# STM32H730_PINOUT.net
KiCad netlist of a schematic drawn in Altium Designer
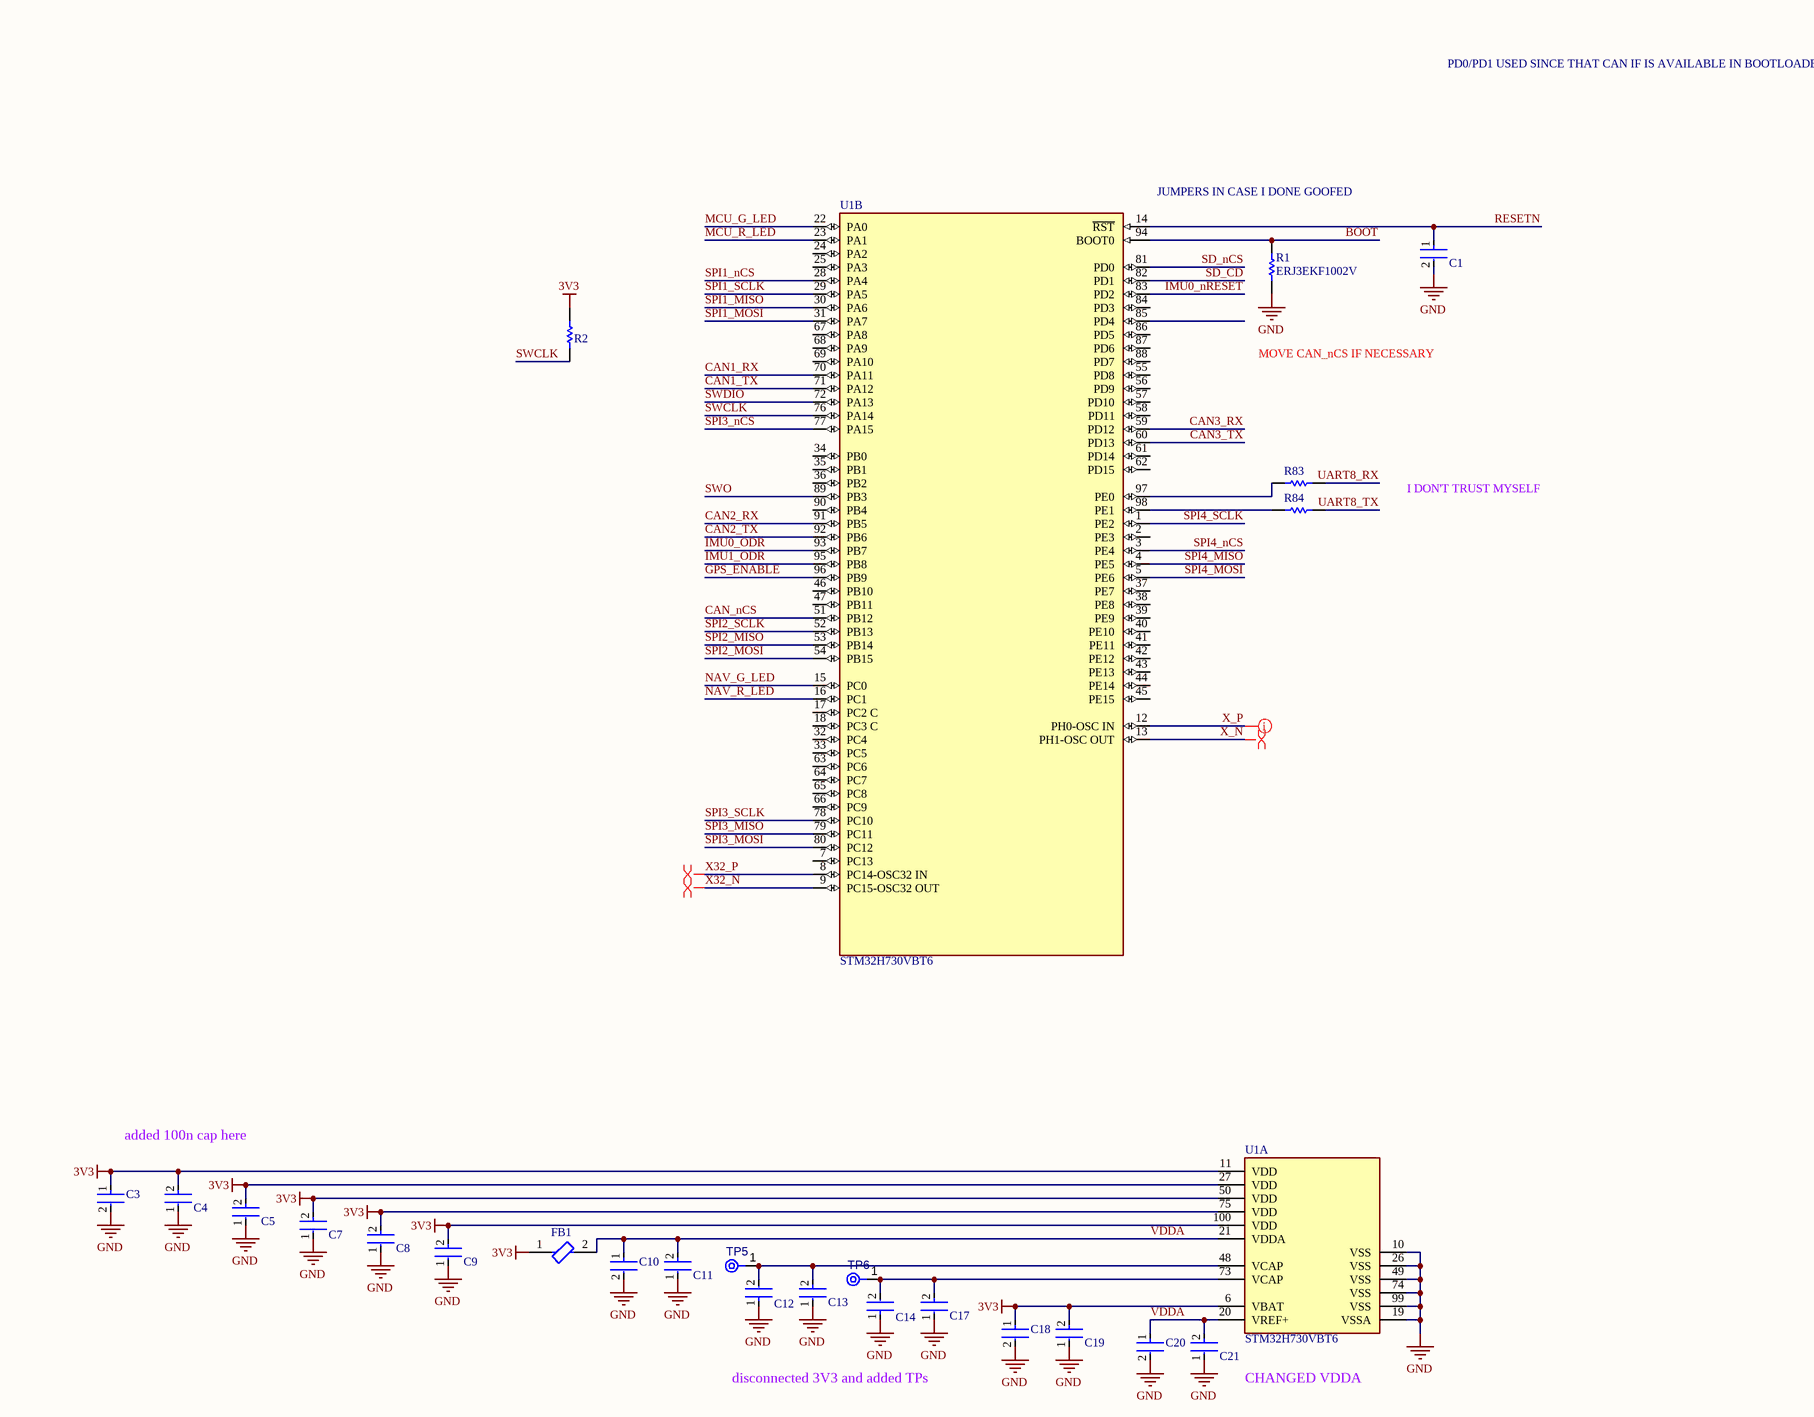
[diagram p0: STM32H730_PINOUT.SchDoc, top left]
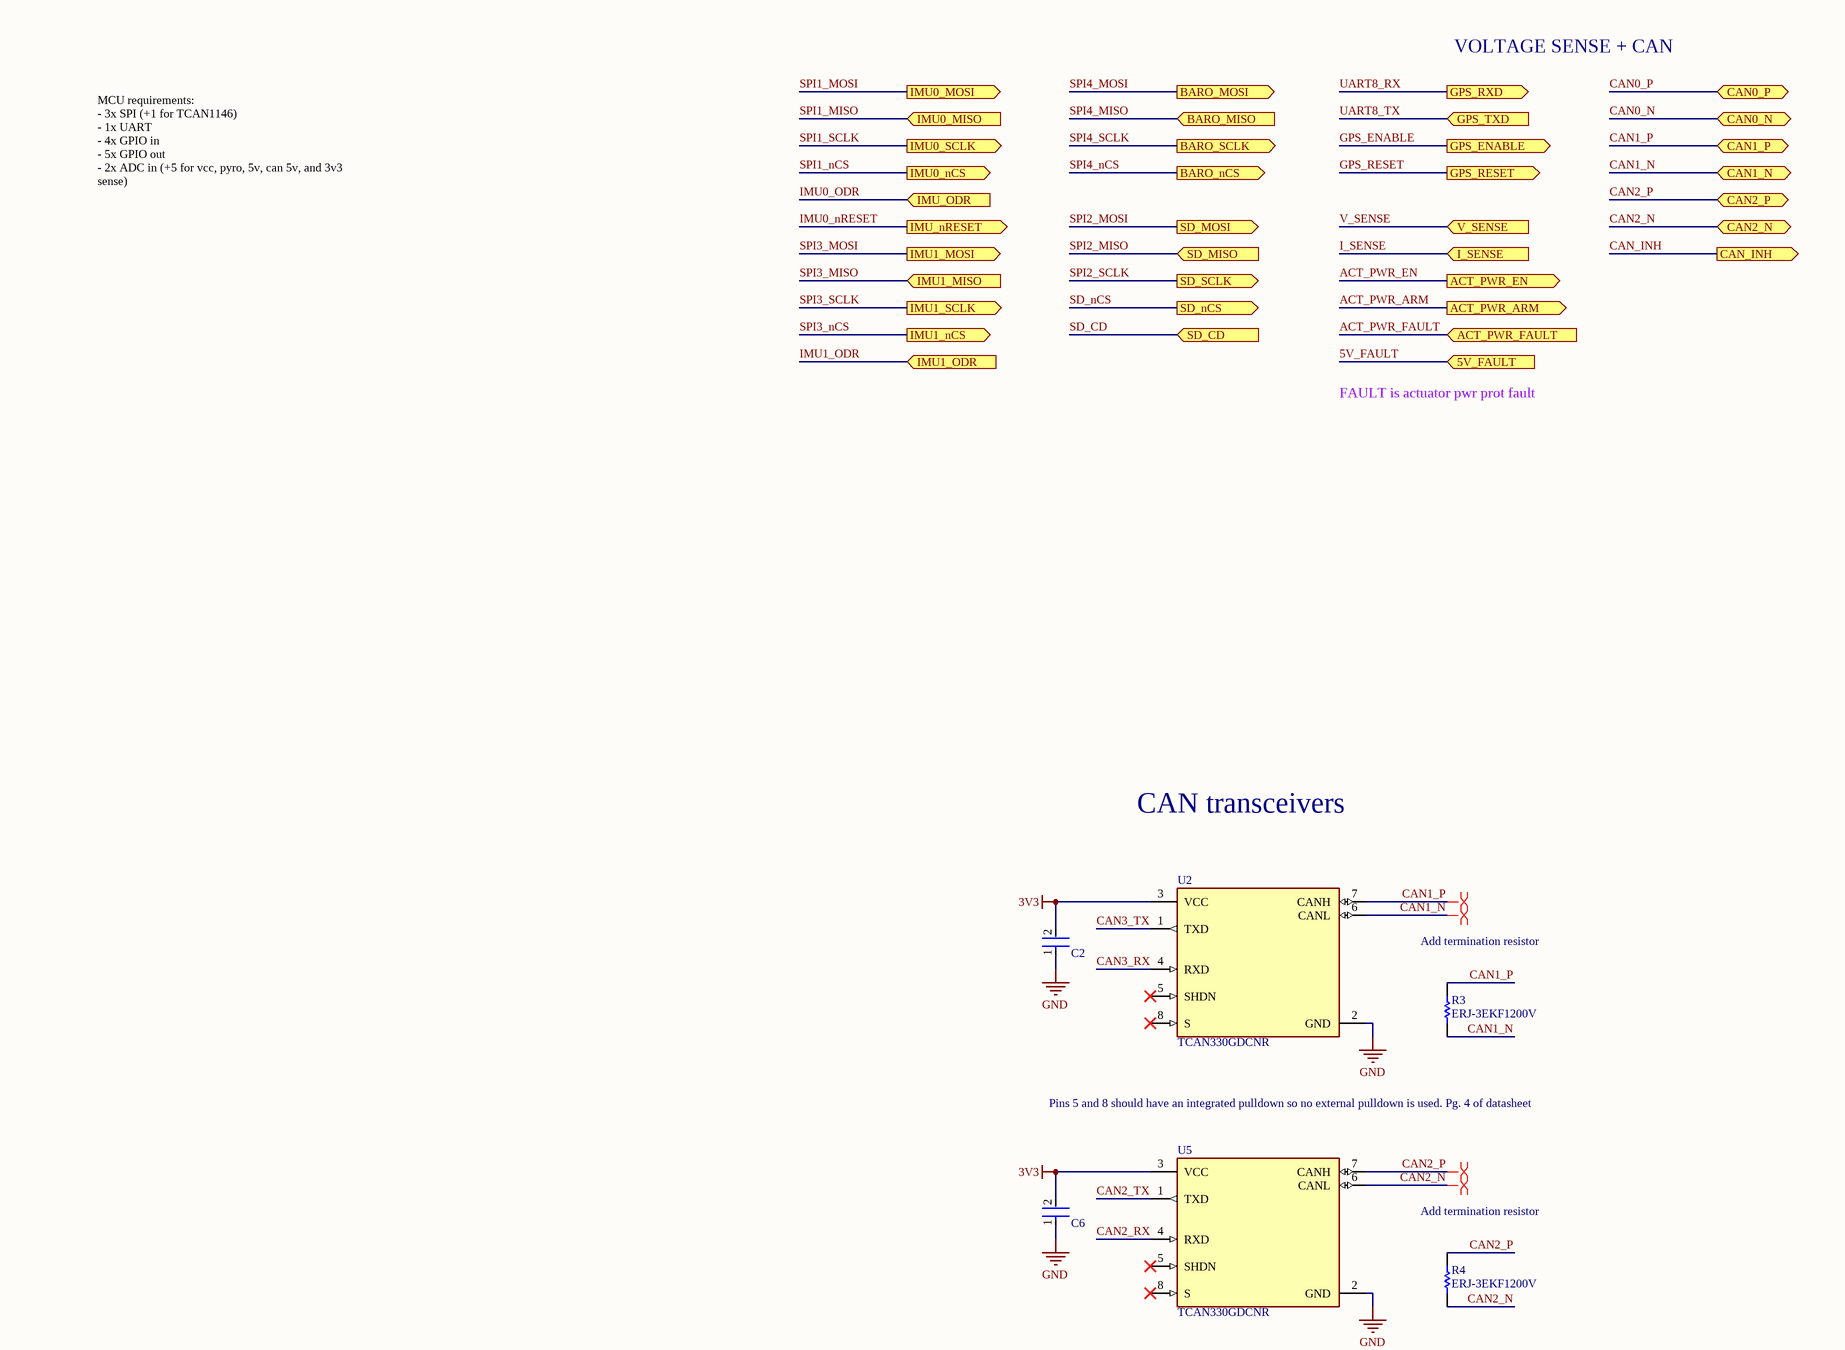
[diagram p1: STM32H730_PINOUT.SchDoc, top right]
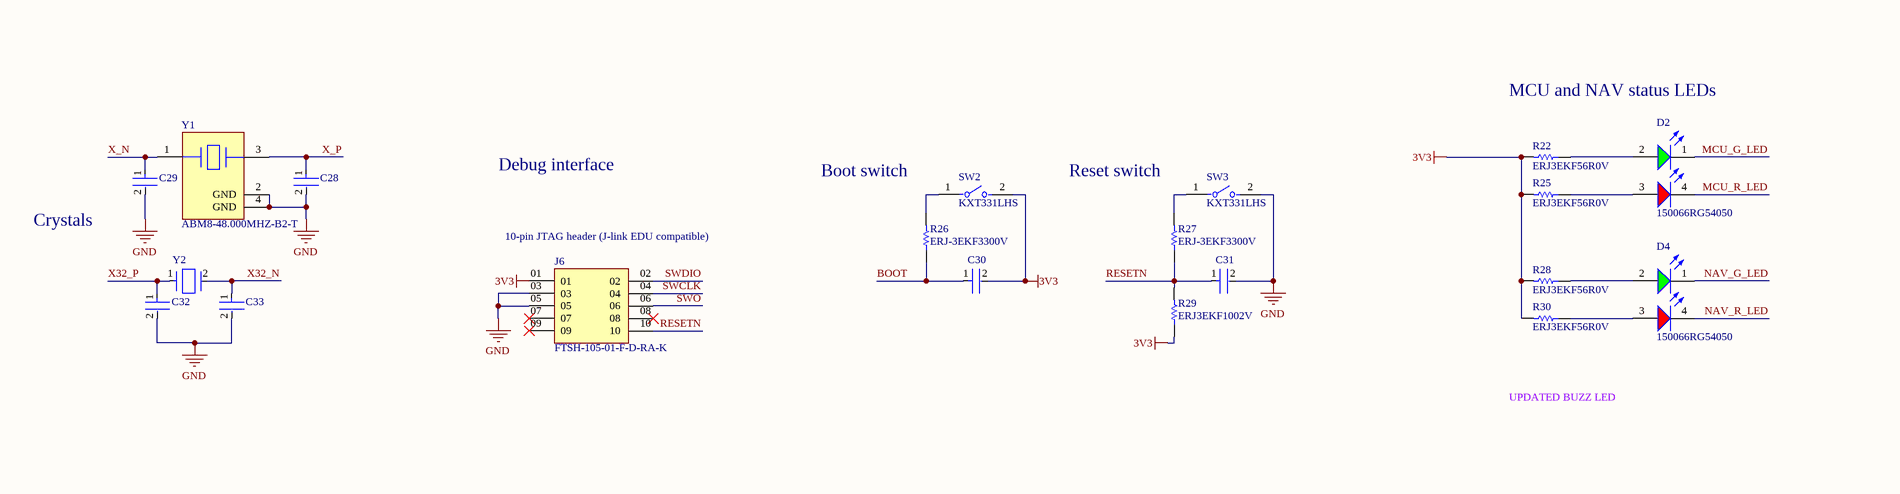
[diagram p2: STM32H730_PINOUT.SchDoc, bottom left]
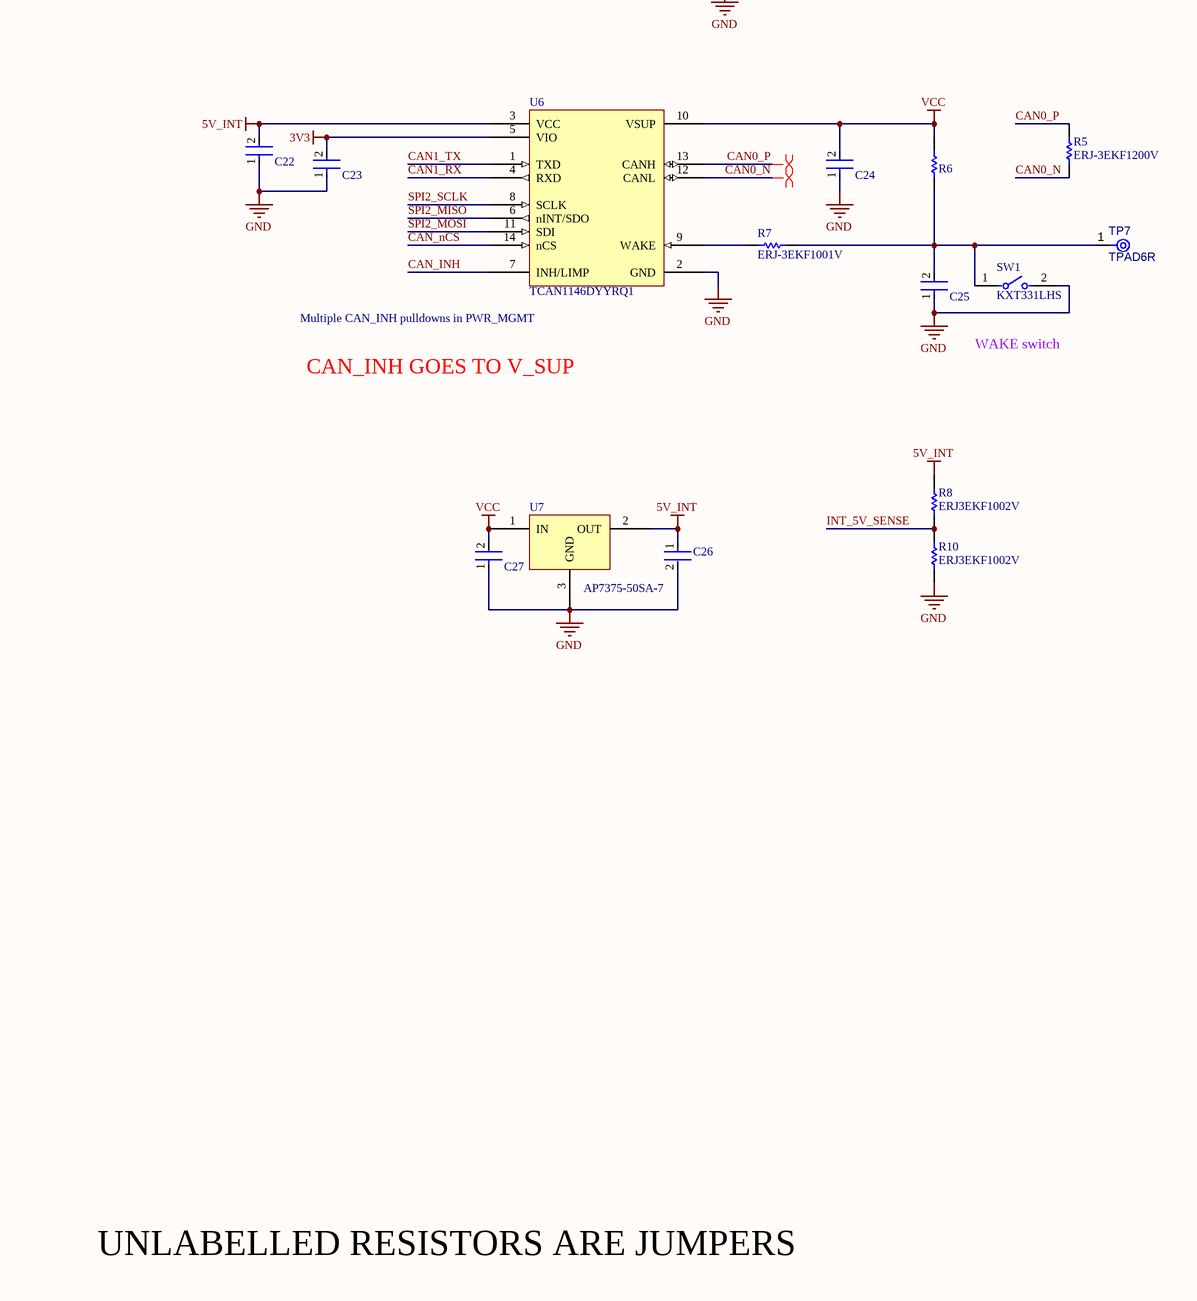
[diagram p3: STM32H730_PINOUT.SchDoc, bottom right]

(export (version "E")
  (design (tool "Eeschema 10.0.6"))
  (components
    (comp (ref "C1")
      (value "C0402C104K8PACTU")
      (footprint "FP-C0402-BB-MFG")
      (description "CAP CER 0.1UF 10V X5R 0402")
      (fields (field (name "MANUFACTURER") "Kemet") (field (name "TOLERANCE") "0.1"))
      (libsource (lib "Altium Content Vault") (part "b4654b650e69147ec39a6b967a45e02"))
    )
    (comp (ref "C2")
      (value "C0402C104K8PACTU")
      (footprint "FP-C0402-BB-MFG")
      (description "CAP CER 0.1UF 10V X5R 0402")
      (fields (field (name "MANUFACTURER") "Kemet") (field (name "TOLERANCE") "0.1"))
      (libsource (lib "Altium Content Vault") (part "b4654b650e69147ec39a6b967a45e02"))
    )
    (comp (ref "C3")
      (value "C1005X5R1A475K050BC")
      (footprint "FP-C1005-050-0_15-MFG")
      (description "CAP CER 4.7UF 10V X5R 0402")
      (fields (field (name "TOLERANCE") "10%"))
      (libsource (lib "Altium Content Vault") (part "b4654b650e69147ec39a6b967a45e02"))
    )
    (comp (ref "C4")
      (value "GRM155R71C104KA88D")
      (footprint "FP-GRM15-MFG")
      (description "CAP CER 0.1UF 16V X7R 0402")
      (fields
        (field (name "TOLERANCE") "10%")
        (field (name "OCTOPART") "https://octopart.com/grm155r71c104ka88d-murata-196880")
      )
      (libsource (lib "Altium Content Vault") (part "236180d848d6139a670b325ea6854c9"))
    )
    (comp (ref "C5")
      (value "GRM155R71C104KA88D")
      (footprint "FP-GRM15-MFG")
      (description "CAP CER 0.1UF 16V X7R 0402")
      (fields
        (field (name "TOLERANCE") "10%")
        (field (name "OCTOPART") "https://octopart.com/grm155r71c104ka88d-murata-196880")
      )
      (libsource (lib "Altium Content Vault") (part "236180d848d6139a670b325ea6854c9"))
    )
    (comp (ref "C6")
      (value "C0402C104K8PACTU")
      (footprint "FP-C0402-BB-MFG")
      (description "CAP CER 0.1UF 10V X5R 0402")
      (fields (field (name "MANUFACTURER") "Kemet") (field (name "TOLERANCE") "0.1"))
      (libsource (lib "Altium Content Vault") (part "b4654b650e69147ec39a6b967a45e02"))
    )
    (comp (ref "C7")
      (value "GRM155R71C104KA88D")
      (footprint "FP-GRM15-MFG")
      (description "CAP CER 0.1UF 16V X7R 0402")
      (fields
        (field (name "TOLERANCE") "10%")
        (field (name "OCTOPART") "https://octopart.com/grm155r71c104ka88d-murata-196880")
      )
      (libsource (lib "Altium Content Vault") (part "236180d848d6139a670b325ea6854c9"))
    )
    (comp (ref "C8")
      (value "GRM155R71C104KA88D")
      (footprint "FP-GRM15-MFG")
      (description "CAP CER 0.1UF 16V X7R 0402")
      (fields
        (field (name "TOLERANCE") "10%")
        (field (name "OCTOPART") "https://octopart.com/grm155r71c104ka88d-murata-196880")
      )
      (libsource (lib "Altium Content Vault") (part "236180d848d6139a670b325ea6854c9"))
    )
    (comp (ref "C9")
      (value "GRM155R71C104KA88D")
      (footprint "FP-GRM15-MFG")
      (description "CAP CER 0.1UF 16V X7R 0402")
      (fields
        (field (name "TOLERANCE") "10%")
        (field (name "OCTOPART") "https://octopart.com/grm155r71c104ka88d-murata-196880")
      )
      (libsource (lib "Altium Content Vault") (part "236180d848d6139a670b325ea6854c9"))
    )
    (comp (ref "C10")
      (value "EMK105BJ105KV-F")
      (footprint "FP-0402-L_1_0_0_05-W_0_5-IPC_A")
      (description "None")
      (fields (field (name "TOLERANCE") "10%"))
      (libsource (lib "Altium Content Vault") (part "b4654b650e69147ec39a6b967a45e02"))
    )
    (comp (ref "C11")
      (value "GRM155R71C104KA88D")
      (footprint "FP-GRM15-MFG")
      (description "CAP CER 0.1UF 16V X7R 0402")
      (fields
        (field (name "TOLERANCE") "10%")
        (field (name "OCTOPART") "https://octopart.com/grm155r71c104ka88d-murata-196880")
      )
      (libsource (lib "Altium Content Vault") (part "236180d848d6139a670b325ea6854c9"))
    )
    (comp (ref "C12")
      (value "C1005X7S1A225K050BC")
      (footprint "FP-C1005-050-0_15-0_1-MFG")
      (description "CAP CER 2.2UF 10V X7S 0402")
      (fields (field (name "TOLERANCE") "10%"))
      (libsource (lib "Altium Content Vault") (part "b4654b650e69147ec39a6b967a45e02"))
    )
    (comp (ref "C13")
      (value "GRM155R71C104KA88D")
      (footprint "FP-GRM15-MFG")
      (description "CAP CER 0.1UF 16V X7R 0402")
      (fields
        (field (name "TOLERANCE") "10%")
        (field (name "OCTOPART") "https://octopart.com/grm155r71c104ka88d-murata-196880")
      )
      (libsource (lib "Altium Content Vault") (part "236180d848d6139a670b325ea6854c9"))
    )
    (comp (ref "C14")
      (value "C1005X7S1A225K050BC")
      (footprint "FP-C1005-050-0_15-0_1-MFG")
      (description "CAP CER 2.2UF 10V X7S 0402")
      (fields (field (name "TOLERANCE") "10%"))
      (libsource (lib "Altium Content Vault") (part "b4654b650e69147ec39a6b967a45e02"))
    )
    (comp (ref "C17")
      (value "GRM155R71C104KA88D")
      (footprint "FP-GRM15-MFG")
      (description "CAP CER 0.1UF 16V X7R 0402")
      (fields
        (field (name "TOLERANCE") "10%")
        (field (name "OCTOPART") "https://octopart.com/grm155r71c104ka88d-murata-196880")
      )
      (libsource (lib "Altium Content Vault") (part "236180d848d6139a670b325ea6854c9"))
    )
    (comp (ref "C18")
      (value "EMK105BJ105KV-F")
      (footprint "FP-0402-L_1_0_0_05-W_0_5-IPC_A")
      (description "None")
      (fields (field (name "TOLERANCE") "10%"))
      (libsource (lib "Altium Content Vault") (part "b4654b650e69147ec39a6b967a45e02"))
    )
    (comp (ref "C19")
      (value "GRM155R71C104KA88D")
      (footprint "FP-GRM15-MFG")
      (description "CAP CER 0.1UF 16V X7R 0402")
      (fields
        (field (name "TOLERANCE") "10%")
        (field (name "OCTOPART") "https://octopart.com/grm155r71c104ka88d-murata-196880")
      )
      (libsource (lib "Altium Content Vault") (part "236180d848d6139a670b325ea6854c9"))
    )
    (comp (ref "C20")
      (value "EMK105BJ105KV-F")
      (footprint "FP-0402-L_1_0_0_05-W_0_5-IPC_A")
      (description "None")
      (fields (field (name "TOLERANCE") "10%"))
      (libsource (lib "Altium Content Vault") (part "b4654b650e69147ec39a6b967a45e02"))
    )
    (comp (ref "C21")
      (value "GRM155R71C104KA88D")
      (footprint "FP-GRM15-MFG")
      (description "CAP CER 0.1UF 16V X7R 0402")
      (fields
        (field (name "TOLERANCE") "10%")
        (field (name "OCTOPART") "https://octopart.com/grm155r71c104ka88d-murata-196880")
      )
      (libsource (lib "Altium Content Vault") (part "236180d848d6139a670b325ea6854c9"))
    )
    (comp (ref "C22")
      (value "C0402C104K8PACTU")
      (footprint "FP-C0402-BB-MFG")
      (description "CAP CER 0.1UF 10V X5R 0402")
      (fields (field (name "MANUFACTURER") "Kemet") (field (name "TOLERANCE") "0.1"))
      (libsource (lib "Altium Content Vault") (part "b4654b650e69147ec39a6b967a45e02"))
    )
    (comp (ref "C23")
      (value "C0402C104K8PACTU")
      (footprint "FP-C0402-BB-MFG")
      (description "CAP CER 0.1UF 10V X5R 0402")
      (fields (field (name "MANUFACTURER") "Kemet") (field (name "TOLERANCE") "0.1"))
      (libsource (lib "Altium Content Vault") (part "b4654b650e69147ec39a6b967a45e02"))
    )
    (comp (ref "C24")
      (value "C0402C104K8PACTU")
      (footprint "FP-C0402-BB-MFG")
      (description "CAP CER 0.1UF 10V X5R 0402")
      (fields (field (name "MANUFACTURER") "Kemet") (field (name "TOLERANCE") "0.1"))
      (libsource (lib "Altium Content Vault") (part "b4654b650e69147ec39a6b967a45e02"))
    )
    (comp (ref "C25")
      (value "C0402C104K8PACTU")
      (footprint "FP-C0402-BB-MFG")
      (description "CAP CER 0.1UF 10V X5R 0402")
      (fields (field (name "MANUFACTURER") "Kemet") (field (name "TOLERANCE") "0.1"))
      (libsource (lib "Altium Content Vault") (part "b4654b650e69147ec39a6b967a45e02"))
    )
    (comp (ref "C26")
      (value "CL05A106MP5NUNC")
      (footprint "FP-CL05A106MP5NUNC-MFG")
      (description "CAP CER 10UF 10V X5R 0402")
      (fields
        (field (name "OCTOPART") "https://octopart.com/cl05a106mp5nunc-samsung-22457395")
        (field (name "TOLERANCE") "20%")
      )
      (libsource (lib "Altium Content Vault") (part "b4654b650e69147ec39a6b967a45e02"))
    )
    (comp (ref "C27")
      (value "C0402C104K8PACTU")
      (footprint "FP-C0402-BB-MFG")
      (description "CAP CER 0.1UF 10V X5R 0402")
      (fields (field (name "MANUFACTURER") "Kemet") (field (name "TOLERANCE") "0.1"))
      (libsource (lib "Altium Content Vault") (part "b4654b650e69147ec39a6b967a45e02"))
    )
    (comp (ref "C28")
      (value "C0402C689C5GACTU")
      (footprint "FP-C0402-BB-MFG")
      (description "CAP CER 6.8PF 50V NP0 0402")
      (fields
        (field (name "OCTOPART") "https://octopart.com/c0402c689c5gactu-kemet-9143567")
        (field (name "MANUFACTURER") "Kemet")
      )
      (libsource (lib "Altium Content Vault") (part "b4654b650e69147ec39a6b967a45e02"))
    )
    (comp (ref "C29")
      (value "C0402C689C5GACTU")
      (footprint "FP-C0402-BB-MFG")
      (description "CAP CER 6.8PF 50V NP0 0402")
      (fields
        (field (name "OCTOPART") "https://octopart.com/c0402c689c5gactu-kemet-9143567")
        (field (name "MANUFACTURER") "Kemet")
      )
      (libsource (lib "Altium Content Vault") (part "b4654b650e69147ec39a6b967a45e02"))
    )
    (comp (ref "C30")
      (value "C0402C104K8PACTU")
      (footprint "FP-C0402-BB-MFG")
      (description "CAP CER 0.1UF 10V X5R 0402")
      (fields (field (name "MANUFACTURER") "Kemet") (field (name "TOLERANCE") "0.1"))
      (libsource (lib "Altium Content Vault") (part "b4654b650e69147ec39a6b967a45e02"))
    )
    (comp (ref "C31")
      (value "C0402C104K8PACTU")
      (footprint "FP-C0402-BB-MFG")
      (description "CAP CER 0.1UF 10V X5R 0402")
      (fields (field (name "MANUFACTURER") "Kemet") (field (name "TOLERANCE") "0.1"))
      (libsource (lib "Altium Content Vault") (part "b4654b650e69147ec39a6b967a45e02"))
    )
    (comp (ref "C32")
      (value "04025A180FAT2A")
      (footprint "FP-0402-L_1_0_1-W_0_5_0_1-IPC_A")
      (description "General Purpose Ceramic Capacitor, 0402, 18pF, 1%, C0G, 30ppm/°C, 50V")
      (fields (field (name "TOLERANCE") "1%"))
      (libsource (lib "Altium Content Vault") (part "b4654b650e69147ec39a6b967a45e02"))
    )
    (comp (ref "C33")
      (value "04025A180FAT2A")
      (footprint "FP-0402-L_1_0_1-W_0_5_0_1-IPC_A")
      (description "General Purpose Ceramic Capacitor, 0402, 18pF, 1%, C0G, 30ppm/°C, 50V")
      (fields (field (name "TOLERANCE") "1%"))
      (libsource (lib "Altium Content Vault") (part "b4654b650e69147ec39a6b967a45e02"))
    )
    (comp (ref "D2")
      (value "150066RG54050")
      (footprint "WL-SBCD_0606")
      (description "Led, Red/Grn, 180Mcd/230Mcd, 624Nm/525Nm Rohs Compliant: Yes")
      (fields (field (name "SOURCE") "rgled.SchLib"))
      (libsource (lib "Space Concordia") (part "CMP-004-00034-2"))
    )
    (comp (ref "D4")
      (value "150066RG54050")
      (footprint "WL-SBCD_0606")
      (description "Led, Red/Grn, 180Mcd/230Mcd, 624Nm/525Nm Rohs Compliant: Yes")
      (fields (field (name "SOURCE") "rgled.SchLib"))
      (libsource (lib "Space Concordia") (part "CMP-004-00034-2"))
    )
    (comp (ref "FB1")
      (value "BLM15PX601SN1D")
      (footprint "FP-BLM15-0_05-MFG")
      (description "Chip Ferrite Bead, 0402, 600Ω @ 100MHz, 0.23Ω, 25%, 900mA")
      (fields (field (name "TOLERANCE") "25%"))
      (libsource (lib "Altium Content Vault") (part "5f30dd21d616792df468990f7003faa"))
    )
    (comp (ref "J6")
      (value "FTSH-105-01-F-D-RA-K")
      (footprint "FTSH-105-01-F-D-RA-K-Footprint-1")
      (libsource (lib "Space Concordia") (part "FTSH-105-01-F-D-RA-K-Symbol-1"))
    )
    (comp (ref "R1")
      (value "ERJ3EKF1002V")
      (footprint "RESC1609X55X30LL15T15")
      (description "Chip Resistor, 10 KOhm, +/- 1%, 0.1 W, -55 to 155 degC, 0603 (1608 Metric), RoHS, Tape and Reel")
      (fields (field (name "TOLERANCE") "1%") (field (name "MANUFACTURER") "Panasonic"))
      (libsource (lib "Altium Content Vault") (part "RES-2"))
    )
    (comp (ref "R2")
      (value "ERJ3EKF1002V")
      (footprint "RESC1609X55X30LL15T15")
      (description "Chip Resistor, 10 KOhm, +/- 1%, 0.1 W, -55 to 155 degC, 0603 (1608 Metric), RoHS, Tape and Reel")
      (fields (field (name "TOLERANCE") "1%") (field (name "MANUFACTURER") "Panasonic"))
      (libsource (lib "Altium Content Vault") (part "RES-2"))
    )
    (comp (ref "R3")
      (value "ERJ-3EKF1200V")
      (footprint "RESC1609X55X30ML15T15")
      (description "Chip Resistor, 120 Ohm, +/- 1%, 0.1 W, -55 to 155 degC, 0603 (1608 Metric), RoHS, Tape and Reel")
      (fields (field (name "TOLERANCE") "1%") (field (name "MANUFACTURER") "Panasonic"))
      (libsource (lib "Altium Content Vault") (part "RES-2"))
    )
    (comp (ref "R4")
      (value "ERJ-3EKF1200V")
      (footprint "RESC1609X55X30ML15T15")
      (description "Chip Resistor, 120 Ohm, +/- 1%, 0.1 W, -55 to 155 degC, 0603 (1608 Metric), RoHS, Tape and Reel")
      (fields (field (name "TOLERANCE") "1%") (field (name "MANUFACTURER") "Panasonic"))
      (libsource (lib "Altium Content Vault") (part "RES-2"))
    )
    (comp (ref "R5")
      (value "ERJ-3EKF1200V")
      (footprint "RESC1609X55X30ML15T15")
      (description "Chip Resistor, 120 Ohm, +/- 1%, 0.1 W, -55 to 155 degC, 0603 (1608 Metric), RoHS, Tape and Reel")
      (fields (field (name "TOLERANCE") "1%") (field (name "MANUFACTURER") "Panasonic"))
      (libsource (lib "Altium Content Vault") (part "RES-2"))
    )
    (comp (ref "R6")
      (value "ERJ3EKF1002V")
      (footprint "RESC1609X55X30LL15T15")
      (description "Chip Resistor, 10 KOhm, +/- 1%, 0.1 W, -55 to 155 degC, 0603 (1608 Metric), RoHS, Tape and Reel")
      (fields (field (name "TOLERANCE") "1%") (field (name "MANUFACTURER") "Panasonic"))
      (libsource (lib "Altium Content Vault") (part "RES-2"))
    )
    (comp (ref "R7")
      (value "ERJ-3EKF1001V")
      (footprint "RESC1608X55X30LL15T15")
      (fields (field (name "MANUFACTURER") "Panasonic"))
      (libsource (lib "Altium Content Vault") (part "RES"))
    )
    (comp (ref "R8")
      (value "ERJ3EKF1002V")
      (footprint "RESC1609X55X30LL15T15")
      (description "Chip Resistor, 10 KOhm, +/- 1%, 0.1 W, -55 to 155 degC, 0603 (1608 Metric), RoHS, Tape and Reel")
      (fields (field (name "TOLERANCE") "1%") (field (name "MANUFACTURER") "Panasonic"))
      (libsource (lib "Altium Content Vault") (part "RES-2"))
    )
    (comp (ref "R10")
      (value "ERJ3EKF1002V")
      (footprint "RESC1609X55X30LL15T15")
      (description "Chip Resistor, 10 KOhm, +/- 1%, 0.1 W, -55 to 155 degC, 0603 (1608 Metric), RoHS, Tape and Reel")
      (fields (field (name "TOLERANCE") "1%") (field (name "MANUFACTURER") "Panasonic"))
      (libsource (lib "Altium Content Vault") (part "RES-2"))
    )
    (comp (ref "R22")
      (value "ERJ3EKF56R0V")
      (footprint "RESC1608X55X30NL15T15")
      (fields (field (name "MANUFACTURER") "Panasonic"))
      (libsource (lib "Altium Content Vault") (part "RES"))
    )
    (comp (ref "R25")
      (value "ERJ3EKF56R0V")
      (footprint "RESC1608X55X30NL15T15")
      (fields (field (name "MANUFACTURER") "Panasonic"))
      (libsource (lib "Altium Content Vault") (part "RES"))
    )
    (comp (ref "R26")
      (value "ERJ-3EKF3300V")
      (footprint "RESC1608X55X30LL15T15")
      (description "Chip Resistor, 330 Ohm, +/- 1%, 0.1 W, -55 to 155 degC, 0603 (1608 Metric), RoHS, Tape and Reel")
      (libsource (lib "Altium Content Vault") (part "RES-2"))
    )
    (comp (ref "R27")
      (value "ERJ-3EKF3300V")
      (footprint "RESC1608X55X30LL15T15")
      (description "Chip Resistor, 330 Ohm, +/- 1%, 0.1 W, -55 to 155 degC, 0603 (1608 Metric), RoHS, Tape and Reel")
      (libsource (lib "Altium Content Vault") (part "RES-2"))
    )
    (comp (ref "R28")
      (value "ERJ3EKF56R0V")
      (footprint "RESC1608X55X30NL15T15")
      (fields (field (name "MANUFACTURER") "Panasonic"))
      (libsource (lib "Altium Content Vault") (part "RES"))
    )
    (comp (ref "R29")
      (value "ERJ3EKF1002V")
      (footprint "RESC1609X55X30LL15T15")
      (description "Chip Resistor, 10 KOhm, +/- 1%, 0.1 W, -55 to 155 degC, 0603 (1608 Metric), RoHS, Tape and Reel")
      (fields (field (name "TOLERANCE") "1%") (field (name "MANUFACTURER") "Panasonic"))
      (libsource (lib "Altium Content Vault") (part "RES-2"))
    )
    (comp (ref "R30")
      (value "ERJ3EKF56R0V")
      (footprint "RESC1608X55X30NL15T15")
      (fields (field (name "MANUFACTURER") "Panasonic"))
      (libsource (lib "Altium Content Vault") (part "RES"))
    )
    (comp (ref "R83")
      (value "0402 JUMPER")
      (footprint "RESC1005X40X25ML05T05")
      (description "READ THE NAME")
      (libsource (lib "Space Concordia") (part "CMP-009-00206-2"))
    )
    (comp (ref "R84")
      (value "0402 JUMPER")
      (footprint "RESC1005X40X25ML05T05")
      (description "READ THE NAME")
      (libsource (lib "Space Concordia") (part "CMP-009-00206-2"))
    )
    (comp (ref "SW1")
      (value "KXT331LHS")
      (footprint "FP-KXT331LHS-MFG")
      (description "SWITCH TACTILE SPST-NO 0.02A 15V")
      (libsource (lib "Altium Content Vault") (part "bb27bde45df87f1f469753f287ef5ae"))
    )
    (comp (ref "SW2")
      (value "KXT331LHS")
      (footprint "FP-KXT331LHS-MFG")
      (description "SWITCH TACTILE SPST-NO 0.02A 15V")
      (libsource (lib "Altium Content Vault") (part "bb27bde45df87f1f469753f287ef5ae"))
    )
    (comp (ref "SW3")
      (value "KXT331LHS")
      (footprint "FP-KXT331LHS-MFG")
      (description "SWITCH TACTILE SPST-NO 0.02A 15V")
      (libsource (lib "Altium Content Vault") (part "bb27bde45df87f1f469753f287ef5ae"))
    )
    (comp (ref "TP5")
      (value "TPAD6R")
      (footprint "TP06R")
      (description "0.6mm round")
      (libsource (lib "uORocketry Hardware") (part "CMP-001-0001-4"))
    )
    (comp (ref "TP6")
      (value "TPAD6R")
      (footprint "TP06R")
      (description "0.6mm round")
      (libsource (lib "uORocketry Hardware") (part "CMP-001-0001-4"))
    )
    (comp (ref "TP7")
      (value "TPAD6R")
      (footprint "TP06R")
      (description "0.6mm round")
      (libsource (lib "uORocketry Hardware") (part "CMP-001-0001-4"))
    )
    (comp (ref "U1")
      (value "STM32H730VBT6")
      (footprint "FP-LQFP100-1L-IPC_C")
      (description "IC MCU 32BIT 128KB FLASH 100LQFP")
      (libsource (lib "Altium Content Vault") (part "44dc6501260a4d92b846760feb66c20"))
    )
    (comp (ref "U2")
      (value "TCAN330GDCNR")
      (footprint "FP-DCN0008A-MFG")
      (description "IC TRANSCEIVER 1/1 SOT23-8")
      (libsource (lib "Altium Content Vault") (part "22681b49c22ad38c6a4e12e04c36c7a"))
    )
    (comp (ref "U5")
      (value "TCAN330GDCNR")
      (footprint "FP-DCN0008A-MFG")
      (description "IC TRANSCEIVER 1/1 SOT23-8")
      (libsource (lib "Altium Content Vault") (part "22681b49c22ad38c6a4e12e04c36c7a"))
    )
    (comp (ref "U6")
      (value "TCAN1146DYYRQ1")
      (footprint "TCAN1146DYYRQ1-Footprint-1")
      (libsource (lib "Space Concordia") (part "CMP-015-00012-2"))
    )
    (comp (ref "U7")
      (value "AP7375-50SA-7")
      (footprint "AP7375-50SA-7-Footprint-1")
      (description "Ldo Cmos Lowcurr SOT23 T&r 3K")
      (libsource (lib "Space Concordia") (part "AP7375-50SA-7"))
    )
    (comp (ref "Y1")
      (value "ABM8-48.000MHZ-B2-T")
      (footprint "FP-ABM8-MFG")
      (description "Crystal 48MHz ±20ppm 18pF SMD-4 3.2mm x 2.5mm")
      (fields (field (name "TOLERANCE") "20ppm"))
      (libsource (lib "Altium Content Vault") (part "dfdb7f9a12507849fb681da9a70121c"))
    )
    (comp (ref "Y2")
      (value "ECS-.327-12.5-1210-TR")
      (footprint "FP-ECX-1210-MFG")
      (description "CRYSTAL 32.7680KHZ 12.5PF SMD")
      (fields
        (field (name "OCTOPART") "https://octopart.com/ecs-.327-12.5-1210-tr-ecs+international-81221340")
        (field (name "TOLERANCE") "20ppm")
      )
      (libsource (lib "Altium Content Vault") (part "99724985039315a44fd0d1401b84e49"))
    )
  )
  (nets
    (net (code "5") (name "/BOOT") (class "Default")
      (node (ref "C30") (pin "1") (pinfunction "1_1") (pintype "passive"))
      (node (ref "R1") (pin "2") (pinfunction "2_2") (pintype "passive"))
      (node (ref "R26") (pin "1") (pinfunction "1_1") (pintype "passive"))
      (node (ref "U1") (pin "94") (pinfunction "BOOT0_94") (pintype "input"))
    )
    (net (code "6") (name "/CAN0_N") (class "Default")
      (node (ref "R5") (pin "2") (pinfunction "2_2") (pintype "passive"))
      (node (ref "U6") (pin "12") (pinfunction "CANL_12") (pintype "bidirectional"))
    )
    (net (code "7") (name "/CAN0_P") (class "Default")
      (node (ref "R5") (pin "1") (pinfunction "1_1") (pintype "passive"))
      (node (ref "U6") (pin "13") (pinfunction "CANH_13") (pintype "bidirectional"))
    )
    (net (code "8") (name "/CAN1_N") (class "Default")
      (node (ref "R3") (pin "1") (pinfunction "1_1") (pintype "passive"))
      (node (ref "U2") (pin "6") (pinfunction "CANL_6") (pintype "bidirectional"))
    )
    (net (code "9") (name "/CAN1_P") (class "Default")
      (node (ref "R3") (pin "2") (pinfunction "2_2") (pintype "passive"))
      (node (ref "U2") (pin "7") (pinfunction "CANH_7") (pintype "bidirectional"))
    )
    (net (code "10") (name "/CAN1_RX") (class "Default")
      (node (ref "U1") (pin "70") (pinfunction "PA11_70") (pintype "bidirectional"))
      (node (ref "U6") (pin "4") (pinfunction "RXD_4") (pintype "output"))
    )
    (net (code "11") (name "/CAN1_TX") (class "Default")
      (node (ref "U1") (pin "71") (pinfunction "PA12_71") (pintype "bidirectional"))
      (node (ref "U6") (pin "1") (pinfunction "TXD_1") (pintype "input"))
    )
    (net (code "12") (name "/CAN2_N") (class "Default")
      (node (ref "R4") (pin "1") (pinfunction "1_1") (pintype "passive"))
      (node (ref "U5") (pin "6") (pinfunction "CANL_6") (pintype "bidirectional"))
    )
    (net (code "13") (name "/CAN2_P") (class "Default")
      (node (ref "R4") (pin "2") (pinfunction "2_2") (pintype "passive"))
      (node (ref "U5") (pin "7") (pinfunction "CANH_7") (pintype "bidirectional"))
    )
    (net (code "14") (name "/CAN2_RX") (class "Default")
      (node (ref "U1") (pin "91") (pinfunction "PB5_91") (pintype "bidirectional"))
      (node (ref "U5") (pin "4") (pinfunction "RXD_4") (pintype "input"))
    )
    (net (code "15") (name "/CAN2_TX") (class "Default")
      (node (ref "U1") (pin "92") (pinfunction "PB6_92") (pintype "bidirectional"))
      (node (ref "U5") (pin "1") (pinfunction "TXD_1") (pintype "output"))
    )
    (net (code "16") (name "/CAN3_RX") (class "Default")
      (node (ref "U1") (pin "59") (pinfunction "PD12_59") (pintype "bidirectional"))
      (node (ref "U2") (pin "4") (pinfunction "RXD_4") (pintype "input"))
    )
    (net (code "17") (name "/CAN3_TX") (class "Default")
      (node (ref "U1") (pin "60") (pinfunction "PD13_60") (pintype "bidirectional"))
      (node (ref "U2") (pin "1") (pinfunction "TXD_1") (pintype "output"))
    )
    (net (code "18") (name "/CAN_INH") (class "Default")
      (node (ref "U6") (pin "7") (pinfunction "INH/LIMP_7") (pintype "passive"))
    )
    (net (code "19") (name "/CAN_nCS") (class "Default")
      (node (ref "U1") (pin "51") (pinfunction "PB12_51") (pintype "bidirectional"))
      (node (ref "U6") (pin "14") (pinfunction "nCS_14") (pintype "input"))
    )
    (net (code "20") (name "/GPS_ENABLE") (class "Default")
      (node (ref "U1") (pin "96") (pinfunction "PB9_96") (pintype "bidirectional"))
    )
    (net (code "22") (name "/IMU0_ODR") (class "Default")
      (node (ref "U1") (pin "93") (pinfunction "PB7_93") (pintype "bidirectional"))
    )
    (net (code "23") (name "/IMU0_nRESET") (class "Default")
      (node (ref "U1") (pin "83") (pinfunction "PD2_83") (pintype "bidirectional"))
    )
    (net (code "24") (name "/IMU1_ODR") (class "Default")
      (node (ref "U1") (pin "95") (pinfunction "PB8_95") (pintype "bidirectional"))
    )
    (net (code "25") (name "/INT_5V_SENSE") (class "Default")
      (node (ref "R10") (pin "1") (pinfunction "1_1") (pintype "passive"))
      (node (ref "R8") (pin "1") (pinfunction "1_1") (pintype "passive"))
    )
    (net (code "27") (name "/MCU_G_LED") (class "Default")
      (node (ref "D2") (pin "1") (pinfunction "K_1") (pintype "passive"))
      (node (ref "U1") (pin "22") (pinfunction "PA0_22") (pintype "bidirectional"))
    )
    (net (code "28") (name "/MCU_R_LED") (class "Default")
      (node (ref "D2") (pin "4") (pinfunction "K_4") (pintype "passive"))
      (node (ref "U1") (pin "23") (pinfunction "PA1_23") (pintype "bidirectional"))
    )
    (net (code "29") (name "/NAV_G_LED") (class "Default")
      (node (ref "D4") (pin "1") (pinfunction "K_1") (pintype "passive"))
      (node (ref "U1") (pin "15") (pinfunction "PC0_15") (pintype "bidirectional"))
    )
    (net (code "30") (name "/NAV_R_LED") (class "Default")
      (node (ref "D4") (pin "4") (pinfunction "K_4") (pintype "passive"))
      (node (ref "U1") (pin "16") (pinfunction "PC1_16") (pintype "bidirectional"))
    )
    (net (code "31") (name "/RESETN") (class "Default")
      (node (ref "C1") (pin "1") (pinfunction "1_1") (pintype "passive"))
      (node (ref "C31") (pin "1") (pinfunction "1_1") (pintype "passive"))
      (node (ref "J6") (pin "10") (pinfunction "10_10") (pintype "passive"))
      (node (ref "R27") (pin "1") (pinfunction "1_1") (pintype "passive"))
      (node (ref "R29") (pin "2") (pinfunction "2_2") (pintype "passive"))
      (node (ref "U1") (pin "14") (pinfunction "~{RST}_14") (pintype "input"))
    )
    (net (code "32") (name "/SD_CD") (class "Default")
      (node (ref "U1") (pin "82") (pinfunction "PD1_82") (pintype "bidirectional"))
    )
    (net (code "33") (name "/SD_nCS") (class "Default")
      (node (ref "U1") (pin "81") (pinfunction "PD0_81") (pintype "bidirectional"))
    )
    (net (code "34") (name "/SPI1_MISO") (class "Default")
      (node (ref "U1") (pin "30") (pinfunction "PA6_30") (pintype "bidirectional"))
    )
    (net (code "35") (name "/SPI1_MOSI") (class "Default")
      (node (ref "U1") (pin "31") (pinfunction "PA7_31") (pintype "bidirectional"))
    )
    (net (code "36") (name "/SPI1_SCLK") (class "Default")
      (node (ref "U1") (pin "29") (pinfunction "PA5_29") (pintype "bidirectional"))
    )
    (net (code "37") (name "/SPI1_nCS") (class "Default")
      (node (ref "U1") (pin "28") (pinfunction "PA4_28") (pintype "bidirectional"))
    )
    (net (code "38") (name "/SPI2_MISO") (class "Default")
      (node (ref "U1") (pin "53") (pinfunction "PB14_53") (pintype "bidirectional"))
      (node (ref "U6") (pin "6") (pinfunction "nINT/SDO_6") (pintype "output"))
    )
    (net (code "39") (name "/SPI2_MOSI") (class "Default")
      (node (ref "U1") (pin "54") (pinfunction "PB15_54") (pintype "bidirectional"))
      (node (ref "U6") (pin "11") (pinfunction "SDI_11") (pintype "input"))
    )
    (net (code "40") (name "/SPI2_SCLK") (class "Default")
      (node (ref "U1") (pin "52") (pinfunction "PB13_52") (pintype "bidirectional"))
      (node (ref "U6") (pin "8") (pinfunction "SCLK_8") (pintype "input"))
    )
    (net (code "41") (name "/SPI3_MISO") (class "Default")
      (node (ref "U1") (pin "79") (pinfunction "PC11_79") (pintype "bidirectional"))
    )
    (net (code "42") (name "/SPI3_MOSI") (class "Default")
      (node (ref "U1") (pin "80") (pinfunction "PC12_80") (pintype "bidirectional"))
    )
    (net (code "43") (name "/SPI3_SCLK") (class "Default")
      (node (ref "U1") (pin "78") (pinfunction "PC10_78") (pintype "bidirectional"))
    )
    (net (code "44") (name "/SPI3_nCS") (class "Default")
      (node (ref "U1") (pin "77") (pinfunction "PA15_77") (pintype "bidirectional"))
    )
    (net (code "45") (name "/SPI4_MISO") (class "Default")
      (node (ref "U1") (pin "4") (pinfunction "PE5_4") (pintype "bidirectional"))
    )
    (net (code "46") (name "/SPI4_MOSI") (class "Default")
      (node (ref "U1") (pin "5") (pinfunction "PE6_5") (pintype "bidirectional"))
    )
    (net (code "47") (name "/SPI4_SCLK") (class "Default")
      (node (ref "U1") (pin "1") (pinfunction "PE2_1") (pintype "bidirectional"))
    )
    (net (code "48") (name "/SPI4_nCS") (class "Default")
      (node (ref "U1") (pin "3") (pinfunction "PE4_3") (pintype "bidirectional"))
    )
    (net (code "49") (name "/SWCLK") (class "Default")
      (node (ref "J6") (pin "04") (pinfunction "04_04") (pintype "passive"))
      (node (ref "R2") (pin "2") (pinfunction "2_2") (pintype "passive"))
      (node (ref "U1") (pin "76") (pinfunction "PA14_76") (pintype "bidirectional"))
    )
    (net (code "50") (name "/SWDIO") (class "Default")
      (node (ref "J6") (pin "02") (pinfunction "02_02") (pintype "passive"))
      (node (ref "U1") (pin "72") (pinfunction "PA13_72") (pintype "bidirectional"))
    )
    (net (code "51") (name "/SWO") (class "Default")
      (node (ref "J6") (pin "06") (pinfunction "06_06") (pintype "passive"))
      (node (ref "U1") (pin "89") (pinfunction "PB3_89") (pintype "bidirectional"))
    )
    (net (code "52") (name "/UART8_RX") (class "Default")
      (node (ref "R83") (pin "2") (pinfunction "2_2") (pintype "passive"))
    )
    (net (code "53") (name "/UART8_TX") (class "Default")
      (node (ref "R84") (pin "2") (pinfunction "2_2") (pintype "passive"))
    )
    (net (code "54") (name "/VDDA") (class "Default")
      (node (ref "C10") (pin "1") (pinfunction "1_1") (pintype "passive"))
      (node (ref "C11") (pin "2") (pinfunction "2_2") (pintype "passive"))
      (node (ref "C20") (pin "1") (pinfunction "1_1") (pintype "passive"))
      (node (ref "C21") (pin "2") (pinfunction "2_2") (pintype "passive"))
      (node (ref "FB1") (pin "2") (pinfunction "2_2") (pintype "passive"))
      (node (ref "U1") (pin "20") (pinfunction "VREF+_20") (pintype "power_in"))
      (node (ref "U1") (pin "21") (pinfunction "VDDA_21") (pintype "power_in"))
    )
    (net (code "56") (name "/X32_N") (class "Default")
      (node (ref "C33") (pin "1") (pinfunction "1_1") (pintype "passive"))
      (node (ref "U1") (pin "9") (pinfunction "PC15-OSC32_OUT_9") (pintype "bidirectional"))
      (node (ref "Y2") (pin "2") (pinfunction "Out/In_2") (pintype "passive"))
    )
    (net (code "57") (name "/X32_P") (class "Default")
      (node (ref "C32") (pin "1") (pinfunction "1_1") (pintype "passive"))
      (node (ref "U1") (pin "8") (pinfunction "PC14-OSC32_IN_8") (pintype "bidirectional"))
      (node (ref "Y2") (pin "1") (pinfunction "In/Out_1") (pintype "passive"))
    )
    (net (code "58") (name "/X_N") (class "Default")
      (node (ref "C29") (pin "1") (pinfunction "1_1") (pintype "passive"))
      (node (ref "U1") (pin "13") (pinfunction "PH1-OSC_OUT_13") (pintype "bidirectional"))
      (node (ref "Y1") (pin "1") (pinfunction "1_1") (pintype "passive"))
    )
    (net (code "59") (name "/X_P") (class "Default")
      (node (ref "C28") (pin "1") (pinfunction "1_1") (pintype "passive"))
      (node (ref "U1") (pin "12") (pinfunction "PH0-OSC_IN_12") (pintype "bidirectional"))
      (node (ref "Y1") (pin "3") (pinfunction "3_3") (pintype "passive"))
    )
    (net (code "60") (name "3V3") (class "Default")
      (node (ref "C18") (pin "1") (pinfunction "1_1") (pintype "passive"))
      (node (ref "C19") (pin "2") (pinfunction "2_2") (pintype "passive"))
      (node (ref "C2") (pin "2") (pinfunction "2_2") (pintype "passive"))
      (node (ref "C23") (pin "2") (pinfunction "2_2") (pintype "passive"))
      (node (ref "C3") (pin "1") (pinfunction "1_1") (pintype "passive"))
      (node (ref "C30") (pin "2") (pinfunction "2_2") (pintype "passive"))
      (node (ref "C4") (pin "2") (pinfunction "2_2") (pintype "passive"))
      (node (ref "C5") (pin "2") (pinfunction "2_2") (pintype "passive"))
      (node (ref "C6") (pin "2") (pinfunction "2_2") (pintype "passive"))
      (node (ref "C7") (pin "2") (pinfunction "2_2") (pintype "passive"))
      (node (ref "C8") (pin "2") (pinfunction "2_2") (pintype "passive"))
      (node (ref "C9") (pin "2") (pinfunction "2_2") (pintype "passive"))
      (node (ref "FB1") (pin "1") (pinfunction "1_1") (pintype "passive"))
      (node (ref "J6") (pin "01") (pinfunction "01_01") (pintype "passive"))
      (node (ref "R2") (pin "1") (pinfunction "1_1") (pintype "passive"))
      (node (ref "R22") (pin "2") (pinfunction "2_2") (pintype "passive"))
      (node (ref "R25") (pin "2") (pinfunction "2_2") (pintype "passive"))
      (node (ref "R28") (pin "2") (pinfunction "2_2") (pintype "passive"))
      (node (ref "R29") (pin "1") (pinfunction "1_1") (pintype "passive"))
      (node (ref "R30") (pin "2") (pinfunction "2_2") (pintype "passive"))
      (node (ref "SW2") (pin "2") (pinfunction "2_2") (pintype "passive"))
      (node (ref "U1") (pin "100") (pinfunction "VDD_100") (pintype "power_in"))
      (node (ref "U1") (pin "11") (pinfunction "VDD_11") (pintype "power_in"))
      (node (ref "U1") (pin "27") (pinfunction "VDD_27") (pintype "power_in"))
      (node (ref "U1") (pin "50") (pinfunction "VDD_50") (pintype "power_in"))
      (node (ref "U1") (pin "6") (pinfunction "VBAT_6") (pintype "power_in"))
      (node (ref "U1") (pin "75") (pinfunction "VDD_75") (pintype "power_in"))
      (node (ref "U2") (pin "3") (pinfunction "VCC_3") (pintype "power_in"))
      (node (ref "U5") (pin "3") (pinfunction "VCC_3") (pintype "power_in"))
      (node (ref "U6") (pin "5") (pinfunction "VIO_5") (pintype "power_in"))
    )
    (net (code "61") (name "5V_INT") (class "Default")
      (node (ref "C22") (pin "2") (pinfunction "2_2") (pintype "passive"))
      (node (ref "C26") (pin "1") (pinfunction "1_1") (pintype "passive"))
      (node (ref "R8") (pin "2") (pinfunction "2_2") (pintype "passive"))
      (node (ref "U6") (pin "3") (pinfunction "VCC_3") (pintype "power_in"))
      (node (ref "U7") (pin "2") (pinfunction "OUT_2") (pintype "passive"))
    )
    (net (code "62") (name "GND") (class "Default")
      (node (ref "C1") (pin "2") (pinfunction "2_2") (pintype "passive"))
      (node (ref "C10") (pin "2") (pinfunction "2_2") (pintype "passive"))
      (node (ref "C11") (pin "1") (pinfunction "1_1") (pintype "passive"))
      (node (ref "C12") (pin "1") (pinfunction "1_1") (pintype "passive"))
      (node (ref "C13") (pin "1") (pinfunction "1_1") (pintype "passive"))
      (node (ref "C14") (pin "1") (pinfunction "1_1") (pintype "passive"))
      (node (ref "C17") (pin "1") (pinfunction "1_1") (pintype "passive"))
      (node (ref "C18") (pin "2") (pinfunction "2_2") (pintype "passive"))
      (node (ref "C19") (pin "1") (pinfunction "1_1") (pintype "passive"))
      (node (ref "C2") (pin "1") (pinfunction "1_1") (pintype "passive"))
      (node (ref "C20") (pin "2") (pinfunction "2_2") (pintype "passive"))
      (node (ref "C21") (pin "1") (pinfunction "1_1") (pintype "passive"))
      (node (ref "C22") (pin "1") (pinfunction "1_1") (pintype "passive"))
      (node (ref "C23") (pin "1") (pinfunction "1_1") (pintype "passive"))
      (node (ref "C24") (pin "1") (pinfunction "1_1") (pintype "passive"))
      (node (ref "C25") (pin "1") (pinfunction "1_1") (pintype "passive"))
      (node (ref "C26") (pin "2") (pinfunction "2_2") (pintype "passive"))
      (node (ref "C27") (pin "1") (pinfunction "1_1") (pintype "passive"))
      (node (ref "C28") (pin "2") (pinfunction "2_2") (pintype "passive"))
      (node (ref "C29") (pin "2") (pinfunction "2_2") (pintype "passive"))
      (node (ref "C3") (pin "2") (pinfunction "2_2") (pintype "passive"))
      (node (ref "C31") (pin "2") (pinfunction "2_2") (pintype "passive"))
      (node (ref "C32") (pin "2") (pinfunction "2_2") (pintype "passive"))
      (node (ref "C33") (pin "2") (pinfunction "2_2") (pintype "passive"))
      (node (ref "C4") (pin "1") (pinfunction "1_1") (pintype "passive"))
      (node (ref "C5") (pin "1") (pinfunction "1_1") (pintype "passive"))
      (node (ref "C6") (pin "1") (pinfunction "1_1") (pintype "passive"))
      (node (ref "C7") (pin "1") (pinfunction "1_1") (pintype "passive"))
      (node (ref "C8") (pin "1") (pinfunction "1_1") (pintype "passive"))
      (node (ref "C9") (pin "1") (pinfunction "1_1") (pintype "passive"))
      (node (ref "J6") (pin "03") (pinfunction "03_03") (pintype "passive"))
      (node (ref "J6") (pin "05") (pinfunction "05_05") (pintype "passive"))
      (node (ref "R1") (pin "1") (pinfunction "1_1") (pintype "passive"))
      (node (ref "R10") (pin "2") (pinfunction "2_2") (pintype "passive"))
      (node (ref "SW1") (pin "2") (pinfunction "2_2") (pintype "passive"))
      (node (ref "SW3") (pin "2") (pinfunction "2_2") (pintype "passive"))
      (node (ref "U1") (pin "10") (pinfunction "VSS_10") (pintype "power_in"))
      (node (ref "U1") (pin "19") (pinfunction "VSSA_19") (pintype "power_in"))
      (node (ref "U1") (pin "26") (pinfunction "VSS_26") (pintype "power_in"))
      (node (ref "U1") (pin "49") (pinfunction "VSS_49") (pintype "power_in"))
      (node (ref "U1") (pin "74") (pinfunction "VSS_74") (pintype "power_in"))
      (node (ref "U1") (pin "99") (pinfunction "VSS_99") (pintype "power_in"))
      (node (ref "U2") (pin "2") (pinfunction "GND_2") (pintype "power_in"))
      (node (ref "U5") (pin "2") (pinfunction "GND_2") (pintype "power_in"))
      (node (ref "U6") (pin "2") (pinfunction "GND_2") (pintype "power_in"))
      (node (ref "U7") (pin "3") (pinfunction "GND_3") (pintype "passive"))
      (node (ref "Y1") (pin "2") (pinfunction "GND_2") (pintype "power_in"))
      (node (ref "Y1") (pin "4") (pinfunction "GND_4") (pintype "power_in"))
    )
    (net (code "63") (name "Net-(D2-A-Pad2)") (class "Default")
      (node (ref "D2") (pin "2") (pinfunction "A_2") (pintype "passive"))
      (node (ref "R22") (pin "1") (pinfunction "1_1") (pintype "passive"))
    )
    (net (code "64") (name "Net-(D2-A-Pad3)") (class "Default")
      (node (ref "D2") (pin "3") (pinfunction "A_3") (pintype "passive"))
      (node (ref "R25") (pin "1") (pinfunction "1_1") (pintype "passive"))
    )
    (net (code "65") (name "Net-(D4-A-Pad2)") (class "Default")
      (node (ref "D4") (pin "2") (pinfunction "A_2") (pintype "passive"))
      (node (ref "R28") (pin "1") (pinfunction "1_1") (pintype "passive"))
    )
    (net (code "66") (name "Net-(D4-A-Pad3)") (class "Default")
      (node (ref "D4") (pin "3") (pinfunction "A_3") (pintype "passive"))
      (node (ref "R30") (pin "1") (pinfunction "1_1") (pintype "passive"))
    )
    (net (code "67") (name "Net-(R26-Pad2)") (class "Default")
      (node (ref "R26") (pin "2") (pinfunction "2_2") (pintype "passive"))
      (node (ref "SW2") (pin "1") (pinfunction "1_1") (pintype "passive"))
    )
    (net (code "68") (name "Net-(R27-Pad2)") (class "Default")
      (node (ref "R27") (pin "2") (pinfunction "2_2") (pintype "passive"))
      (node (ref "SW3") (pin "1") (pinfunction "1_1") (pintype "passive"))
    )
    (net (code "69") (name "Net-(TP5-TP)") (class "Default")
      (node (ref "C12") (pin "2") (pinfunction "2_2") (pintype "passive"))
      (node (ref "C13") (pin "2") (pinfunction "2_2") (pintype "passive"))
      (node (ref "TP5") (pin "1") (pinfunction "TP_1") (pintype "passive"))
      (node (ref "U1") (pin "48") (pinfunction "VCAP_48") (pintype "power_in"))
    )
    (net (code "70") (name "Net-(TP6-TP)") (class "Default")
      (node (ref "C14") (pin "2") (pinfunction "2_2") (pintype "passive"))
      (node (ref "C17") (pin "2") (pinfunction "2_2") (pintype "passive"))
      (node (ref "TP6") (pin "1") (pinfunction "TP_1") (pintype "passive"))
      (node (ref "U1") (pin "73") (pinfunction "VCAP_73") (pintype "power_in"))
    )
    (net (code "71") (name "Net-(TP7-TP)") (class "Default")
      (node (ref "C25") (pin "2") (pinfunction "2_2") (pintype "passive"))
      (node (ref "R6") (pin "2") (pinfunction "2_2") (pintype "passive"))
      (node (ref "R7") (pin "2") (pinfunction "2_2") (pintype "passive"))
      (node (ref "SW1") (pin "1") (pinfunction "1_1") (pintype "passive"))
      (node (ref "TP7") (pin "1") (pinfunction "TP_1") (pintype "passive"))
    )
    (net (code "72") (name "Net-(U1B-PE0)") (class "Default")
      (node (ref "R83") (pin "1") (pinfunction "1_1") (pintype "passive"))
      (node (ref "U1") (pin "97") (pinfunction "PE0_97") (pintype "bidirectional"))
    )
    (net (code "73") (name "Net-(U1B-PE1)") (class "Default")
      (node (ref "R84") (pin "1") (pinfunction "1_1") (pintype "passive"))
      (node (ref "U1") (pin "98") (pinfunction "PE1_98") (pintype "bidirectional"))
    )
    (net (code "74") (name "Net-(U6-WAKE)") (class "Default")
      (node (ref "R7") (pin "1") (pinfunction "1_1") (pintype "passive"))
      (node (ref "U6") (pin "9") (pinfunction "WAKE_9") (pintype "input"))
    )
    (net (code "75") (name "VCC") (class "Default")
      (node (ref "C24") (pin "2") (pinfunction "2_2") (pintype "passive"))
      (node (ref "C27") (pin "2") (pinfunction "2_2") (pintype "passive"))
      (node (ref "R6") (pin "1") (pinfunction "1_1") (pintype "passive"))
      (node (ref "U6") (pin "10") (pinfunction "VSUP_10") (pintype "power_in"))
      (node (ref "U7") (pin "1") (pinfunction "IN_1") (pintype "passive"))
    )
    (net (code "76") (name "unconnected-(J6-Pad07)") (class "Default")
      (node (ref "J6") (pin "07") (pinfunction "07_07") (pintype "passive+no_connect"))
    )
    (net (code "77") (name "unconnected-(J6-Pad08)") (class "Default")
      (node (ref "J6") (pin "08") (pinfunction "08_08") (pintype "passive+no_connect"))
    )
    (net (code "78") (name "unconnected-(J6-Pad09)") (class "Default")
      (node (ref "J6") (pin "09") (pinfunction "09_09") (pintype "passive+no_connect"))
    )
    (net (code "79") (name "unconnected-(U1B-PA2-Pad24)") (class "Default")
      (node (ref "U1") (pin "24") (pinfunction "PA2_24") (pintype "bidirectional"))
    )
    (net (code "80") (name "unconnected-(U1B-PA3-Pad25)") (class "Default")
      (node (ref "U1") (pin "25") (pinfunction "PA3_25") (pintype "bidirectional"))
    )
    (net (code "81") (name "unconnected-(U1B-PA8-Pad67)") (class "Default")
      (node (ref "U1") (pin "67") (pinfunction "PA8_67") (pintype "bidirectional"))
    )
    (net (code "82") (name "unconnected-(U1B-PA9-Pad68)") (class "Default")
      (node (ref "U1") (pin "68") (pinfunction "PA9_68") (pintype "bidirectional"))
    )
    (net (code "83") (name "unconnected-(U1B-PA10-Pad69)") (class "Default")
      (node (ref "U1") (pin "69") (pinfunction "PA10_69") (pintype "bidirectional"))
    )
    (net (code "84") (name "unconnected-(U1B-PB0-Pad34)") (class "Default")
      (node (ref "U1") (pin "34") (pinfunction "PB0_34") (pintype "bidirectional"))
    )
    (net (code "85") (name "unconnected-(U1B-PB1-Pad35)") (class "Default")
      (node (ref "U1") (pin "35") (pinfunction "PB1_35") (pintype "bidirectional"))
    )
    (net (code "86") (name "unconnected-(U1B-PB2-Pad36)") (class "Default")
      (node (ref "U1") (pin "36") (pinfunction "PB2_36") (pintype "bidirectional"))
    )
    (net (code "87") (name "unconnected-(U1B-PB4-Pad90)") (class "Default")
      (node (ref "U1") (pin "90") (pinfunction "PB4_90") (pintype "bidirectional"))
    )
    (net (code "88") (name "unconnected-(U1B-PB10-Pad46)") (class "Default")
      (node (ref "U1") (pin "46") (pinfunction "PB10_46") (pintype "bidirectional"))
    )
    (net (code "89") (name "unconnected-(U1B-PB11-Pad47)") (class "Default")
      (node (ref "U1") (pin "47") (pinfunction "PB11_47") (pintype "bidirectional"))
    )
    (net (code "90") (name "unconnected-(U1B-PC2_C-Pad17)") (class "Default")
      (node (ref "U1") (pin "17") (pinfunction "PC2_C_17") (pintype "bidirectional"))
    )
    (net (code "91") (name "unconnected-(U1B-PC3_C-Pad18)") (class "Default")
      (node (ref "U1") (pin "18") (pinfunction "PC3_C_18") (pintype "bidirectional"))
    )
    (net (code "92") (name "unconnected-(U1B-PC4-Pad32)") (class "Default")
      (node (ref "U1") (pin "32") (pinfunction "PC4_32") (pintype "bidirectional"))
    )
    (net (code "93") (name "unconnected-(U1B-PC5-Pad33)") (class "Default")
      (node (ref "U1") (pin "33") (pinfunction "PC5_33") (pintype "bidirectional"))
    )
    (net (code "94") (name "unconnected-(U1B-PC6-Pad63)") (class "Default")
      (node (ref "U1") (pin "63") (pinfunction "PC6_63") (pintype "bidirectional"))
    )
    (net (code "95") (name "unconnected-(U1B-PC7-Pad64)") (class "Default")
      (node (ref "U1") (pin "64") (pinfunction "PC7_64") (pintype "bidirectional"))
    )
    (net (code "96") (name "unconnected-(U1B-PC8-Pad65)") (class "Default")
      (node (ref "U1") (pin "65") (pinfunction "PC8_65") (pintype "bidirectional"))
    )
    (net (code "97") (name "unconnected-(U1B-PC9-Pad66)") (class "Default")
      (node (ref "U1") (pin "66") (pinfunction "PC9_66") (pintype "bidirectional"))
    )
    (net (code "98") (name "unconnected-(U1B-PC13-Pad7)") (class "Default")
      (node (ref "U1") (pin "7") (pinfunction "PC13_7") (pintype "bidirectional"))
    )
    (net (code "99") (name "unconnected-(U1B-PD3-Pad84)") (class "Default")
      (node (ref "U1") (pin "84") (pinfunction "PD3_84") (pintype "bidirectional"))
    )
    (net (code "100") (name "unconnected-(U1B-PD4-Pad85)") (class "Default")
      (node (ref "U1") (pin "85") (pinfunction "PD4_85") (pintype "bidirectional"))
    )
    (net (code "101") (name "unconnected-(U1B-PD5-Pad86)") (class "Default")
      (node (ref "U1") (pin "86") (pinfunction "PD5_86") (pintype "bidirectional"))
    )
    (net (code "102") (name "unconnected-(U1B-PD6-Pad87)") (class "Default")
      (node (ref "U1") (pin "87") (pinfunction "PD6_87") (pintype "bidirectional"))
    )
    (net (code "103") (name "unconnected-(U1B-PD7-Pad88)") (class "Default")
      (node (ref "U1") (pin "88") (pinfunction "PD7_88") (pintype "bidirectional"))
    )
    (net (code "104") (name "unconnected-(U1B-PD8-Pad55)") (class "Default")
      (node (ref "U1") (pin "55") (pinfunction "PD8_55") (pintype "bidirectional"))
    )
    (net (code "105") (name "unconnected-(U1B-PD9-Pad56)") (class "Default")
      (node (ref "U1") (pin "56") (pinfunction "PD9_56") (pintype "bidirectional"))
    )
    (net (code "106") (name "unconnected-(U1B-PD10-Pad57)") (class "Default")
      (node (ref "U1") (pin "57") (pinfunction "PD10_57") (pintype "bidirectional"))
    )
    (net (code "107") (name "unconnected-(U1B-PD11-Pad58)") (class "Default")
      (node (ref "U1") (pin "58") (pinfunction "PD11_58") (pintype "bidirectional"))
    )
    (net (code "108") (name "unconnected-(U1B-PD14-Pad61)") (class "Default")
      (node (ref "U1") (pin "61") (pinfunction "PD14_61") (pintype "bidirectional"))
    )
    (net (code "109") (name "unconnected-(U1B-PD15-Pad62)") (class "Default")
      (node (ref "U1") (pin "62") (pinfunction "PD15_62") (pintype "bidirectional"))
    )
    (net (code "110") (name "unconnected-(U1B-PE3-Pad2)") (class "Default")
      (node (ref "U1") (pin "2") (pinfunction "PE3_2") (pintype "bidirectional"))
    )
    (net (code "111") (name "unconnected-(U1B-PE7-Pad37)") (class "Default")
      (node (ref "U1") (pin "37") (pinfunction "PE7_37") (pintype "bidirectional"))
    )
    (net (code "112") (name "unconnected-(U1B-PE8-Pad38)") (class "Default")
      (node (ref "U1") (pin "38") (pinfunction "PE8_38") (pintype "bidirectional"))
    )
    (net (code "113") (name "unconnected-(U1B-PE9-Pad39)") (class "Default")
      (node (ref "U1") (pin "39") (pinfunction "PE9_39") (pintype "bidirectional"))
    )
    (net (code "114") (name "unconnected-(U1B-PE10-Pad40)") (class "Default")
      (node (ref "U1") (pin "40") (pinfunction "PE10_40") (pintype "bidirectional"))
    )
    (net (code "115") (name "unconnected-(U1B-PE11-Pad41)") (class "Default")
      (node (ref "U1") (pin "41") (pinfunction "PE11_41") (pintype "bidirectional"))
    )
    (net (code "116") (name "unconnected-(U1B-PE12-Pad42)") (class "Default")
      (node (ref "U1") (pin "42") (pinfunction "PE12_42") (pintype "bidirectional"))
    )
    (net (code "117") (name "unconnected-(U1B-PE13-Pad43)") (class "Default")
      (node (ref "U1") (pin "43") (pinfunction "PE13_43") (pintype "bidirectional"))
    )
    (net (code "118") (name "unconnected-(U1B-PE14-Pad44)") (class "Default")
      (node (ref "U1") (pin "44") (pinfunction "PE14_44") (pintype "bidirectional"))
    )
    (net (code "119") (name "unconnected-(U1B-PE15-Pad45)") (class "Default")
      (node (ref "U1") (pin "45") (pinfunction "PE15_45") (pintype "bidirectional"))
    )
    (net (code "120") (name "unconnected-(U2-S-Pad8)") (class "Default")
      (node (ref "U2") (pin "8") (pinfunction "S_8") (pintype "input+no_connect"))
    )
    (net (code "121") (name "unconnected-(U2-SHDN-Pad5)") (class "Default")
      (node (ref "U2") (pin "5") (pinfunction "SHDN_5") (pintype "input+no_connect"))
    )
    (net (code "122") (name "unconnected-(U5-S-Pad8)") (class "Default")
      (node (ref "U5") (pin "8") (pinfunction "S_8") (pintype "input+no_connect"))
    )
    (net (code "123") (name "unconnected-(U5-SHDN-Pad5)") (class "Default")
      (node (ref "U5") (pin "5") (pinfunction "SHDN_5") (pintype "input+no_connect"))
    )
  )
)
